# 1-Schematic_Sumo_sensor.net
KiCad netlist of a schematic drawn in EasyEDA
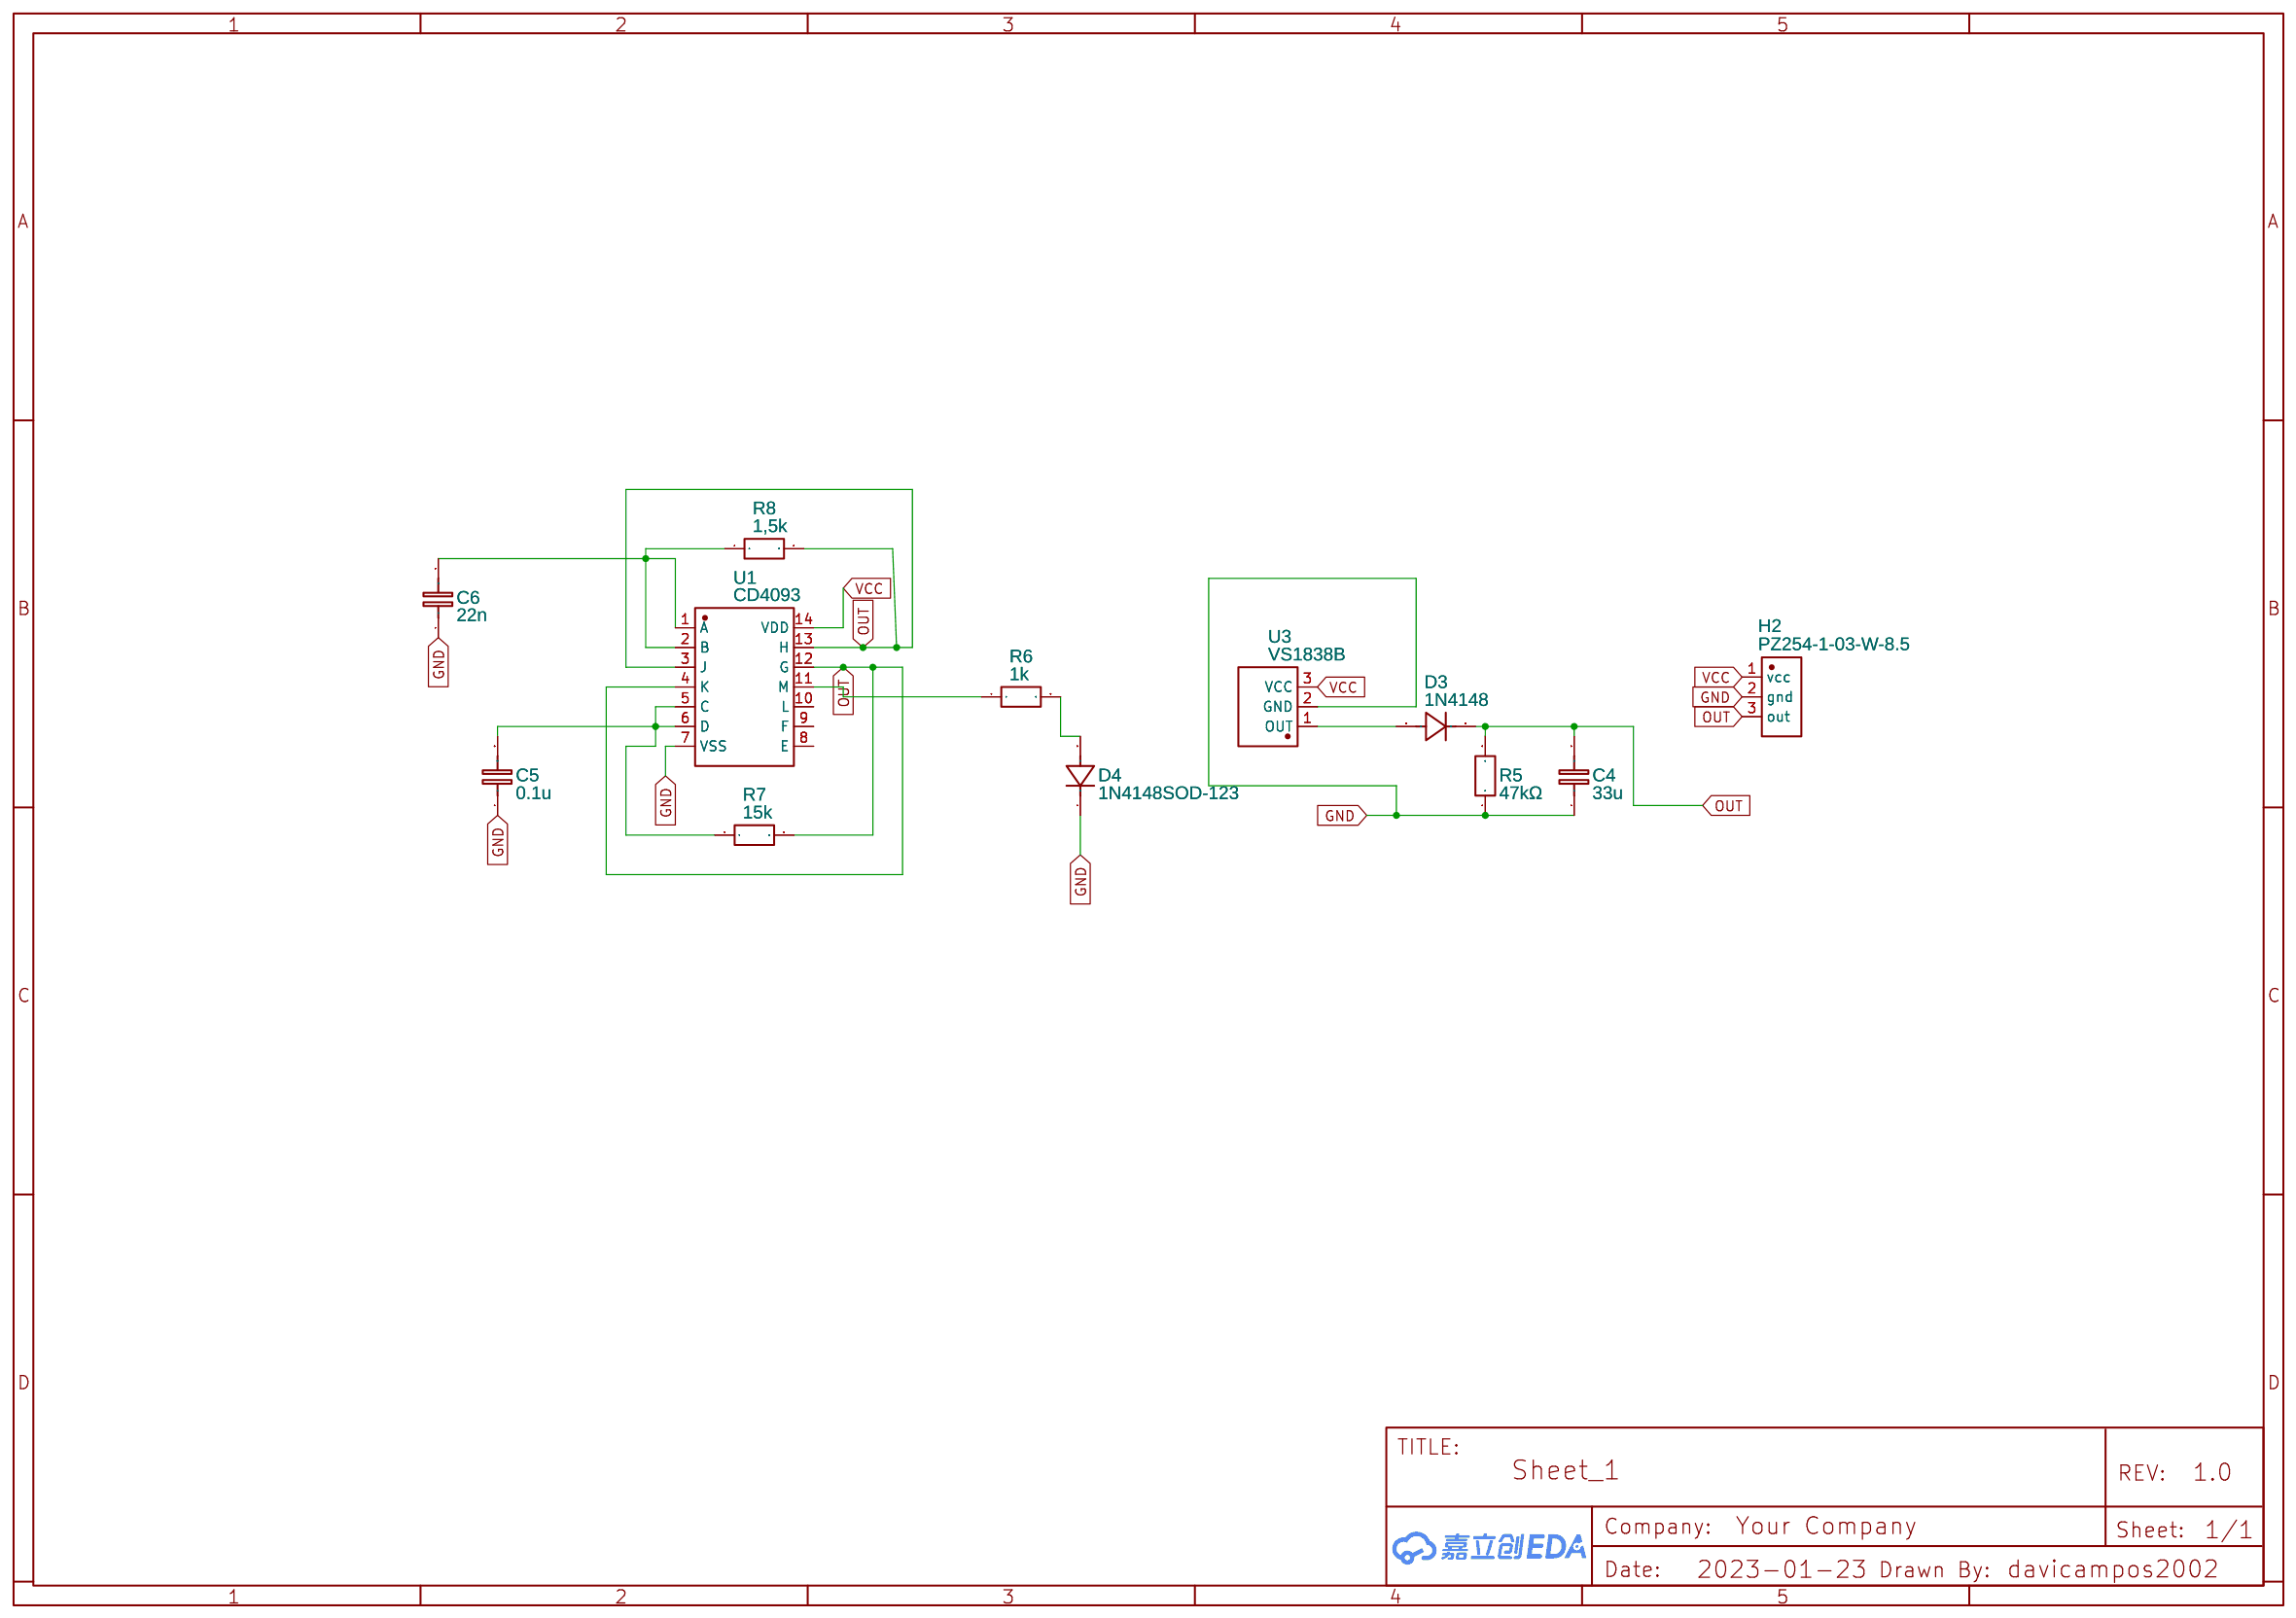
[diagram p0: schematic sheet]

(export (version "E")
  (design (tool "Eeschema 10.0.6"))
  (components
    (comp (ref "C4") (value "33u") (libsource (lib "") (part "C_0603_EU_1")))
    (comp (ref "C5") (value "0.1u") (libsource (lib "") (part "C_0603_EU")))
    (comp (ref "C6") (value "22n") (libsource (lib "") (part "C_0603_EU_2")))
    (comp (ref "D3")
      (value "1N4148")
      (fields
        (field (name "BOM_Manufacturer Part") "1N4148SOD-123")
        (field (name "BOM_Supplier Part") "C2972760")
      )
      (libsource (lib "") (part "1N4148SOD-123"))
    )
    (comp (ref "D4")
      (value "1N4148SOD-123")
      (fields (field (name "BOM_Supplier Part") "C2972760"))
      (libsource (lib "") (part "1N4148SOD-123_1"))
    )
    (comp (ref "H2")
      (value "PZ254-1-03-W-8.5")
      (fields (field (name "BOM_Supplier Part") "C2894945"))
      (libsource (lib "") (part "PZ254-1-03-W-8.5"))
    )
    (comp (ref "R5")
      (value "47kΩ")
      (fields
        (field (name "BOM_Manufacturer Part") "SY0402JN47KP")
        (field (name "BOM_Supplier Part") "C380748")
      )
      (libsource (lib "") (part "SY0402JN47KP"))
    )
    (comp (ref "R6") (value "1k") (libsource (lib "") (part "R_0603_EU")))
    (comp (ref "R7") (value "15k") (libsource (lib "") (part "R_0603_EU")))
    (comp (ref "R8") (value "1,5k") (libsource (lib "") (part "R_0603_EU")))
    (comp (ref "U1")
      (value "CD4093")
      (fields (field (name "BOM_Supplier Part") "C3041280"))
      (libsource (lib "") (part "CD4093"))
    )
    (comp (ref "U3")
      (value "VS1838B")
      (fields (field (name "BOM_Supplier Part") "C9900002107"))
      (libsource (lib "") (part "VS1838B"))
    )
  )
  (nets
    (net (code "1") (name "GND") (class "Default")
      (node (ref "C4") (pin "1") (pinfunction "1_1") (pintype "unspecified"))
      (node (ref "C5") (pin "1") (pinfunction "1_1") (pintype "unspecified"))
      (node (ref "C6") (pin "1") (pinfunction "1_1") (pintype "unspecified"))
      (node (ref "D4") (pin "1") (pinfunction "K_1") (pintype "unspecified"))
      (node (ref "H2") (pin "2") (pinfunction "gnd_2") (pintype "unspecified"))
      (node (ref "R5") (pin "1") (pinfunction "1_1") (pintype "unspecified"))
      (node (ref "U1") (pin "7") (pinfunction "VSS_7") (pintype "unspecified"))
      (node (ref "U3") (pin "2") (pinfunction "GND_2") (pintype "unspecified"))
    )
    (net (code "2") (name "Net-(D3-A)") (class "Default")
      (node (ref "D3") (pin "2") (pinfunction "A_2") (pintype "unspecified"))
      (node (ref "U3") (pin "1") (pinfunction "OUT_1") (pintype "unspecified"))
    )
    (net (code "3") (name "Net-(D4-A)") (class "Default")
      (node (ref "D4") (pin "2") (pinfunction "A_2") (pintype "unspecified"))
      (node (ref "R6") (pin "2") (pinfunction "2_2") (pintype "unspecified"))
    )
    (net (code "4") (name "Net-(U1-A)") (class "Default")
      (node (ref "C6") (pin "2") (pinfunction "2_2") (pintype "unspecified"))
      (node (ref "R8") (pin "1") (pinfunction "1_1") (pintype "unspecified"))
      (node (ref "U1") (pin "1") (pinfunction "A_1") (pintype "unspecified"))
      (node (ref "U1") (pin "2") (pinfunction "B_2") (pintype "unspecified"))
    )
    (net (code "5") (name "Net-(U1-C)") (class "Default")
      (node (ref "C5") (pin "2") (pinfunction "2_2") (pintype "unspecified"))
      (node (ref "R7") (pin "1") (pinfunction "1_1") (pintype "unspecified"))
      (node (ref "U1") (pin "5") (pinfunction "C_5") (pintype "unspecified"))
      (node (ref "U1") (pin "6") (pinfunction "D_6") (pintype "unspecified"))
    )
    (net (code "6") (name "Net-(U1-M)") (class "Default")
      (node (ref "R6") (pin "1") (pinfunction "1_1") (pintype "unspecified"))
      (node (ref "U1") (pin "11") (pinfunction "M_11") (pintype "unspecified"))
    )
    (net (code "7") (name "OUT") (class "Default")
      (node (ref "C4") (pin "2") (pinfunction "2_2") (pintype "unspecified"))
      (node (ref "D3") (pin "1") (pinfunction "K_1") (pintype "unspecified"))
      (node (ref "H2") (pin "3") (pinfunction "out_3") (pintype "unspecified"))
      (node (ref "R5") (pin "2") (pinfunction "2_2") (pintype "unspecified"))
      (node (ref "R7") (pin "2") (pinfunction "2_2") (pintype "unspecified"))
      (node (ref "R8") (pin "2") (pinfunction "2_2") (pintype "unspecified"))
      (node (ref "U1") (pin "12") (pinfunction "G_12") (pintype "unspecified"))
      (node (ref "U1") (pin "13") (pinfunction "H_13") (pintype "unspecified"))
      (node (ref "U1") (pin "3") (pinfunction "J_3") (pintype "unspecified"))
      (node (ref "U1") (pin "4") (pinfunction "K_4") (pintype "unspecified"))
    )
    (net (code "8") (name "VCC") (class "Default")
      (node (ref "H2") (pin "1") (pinfunction "vcc_1") (pintype "unspecified"))
      (node (ref "U1") (pin "14") (pinfunction "VDD_14") (pintype "unspecified"))
      (node (ref "U3") (pin "3") (pinfunction "VCC_3") (pintype "unspecified"))
    )
    (net (code "9") (name "unconnected-(U1-E-Pad8)") (class "Default")
      (node (ref "U1") (pin "8") (pinfunction "E_8") (pintype "unspecified"))
    )
    (net (code "10") (name "unconnected-(U1-F-Pad9)") (class "Default")
      (node (ref "U1") (pin "9") (pinfunction "F_9") (pintype "unspecified"))
    )
    (net (code "11") (name "unconnected-(U1-L-Pad10)") (class "Default")
      (node (ref "U1") (pin "10") (pinfunction "L_10") (pintype "unspecified"))
    )
  )
)
